# schematics.net
KiCad netlist of a schematic drawn in EAGLE
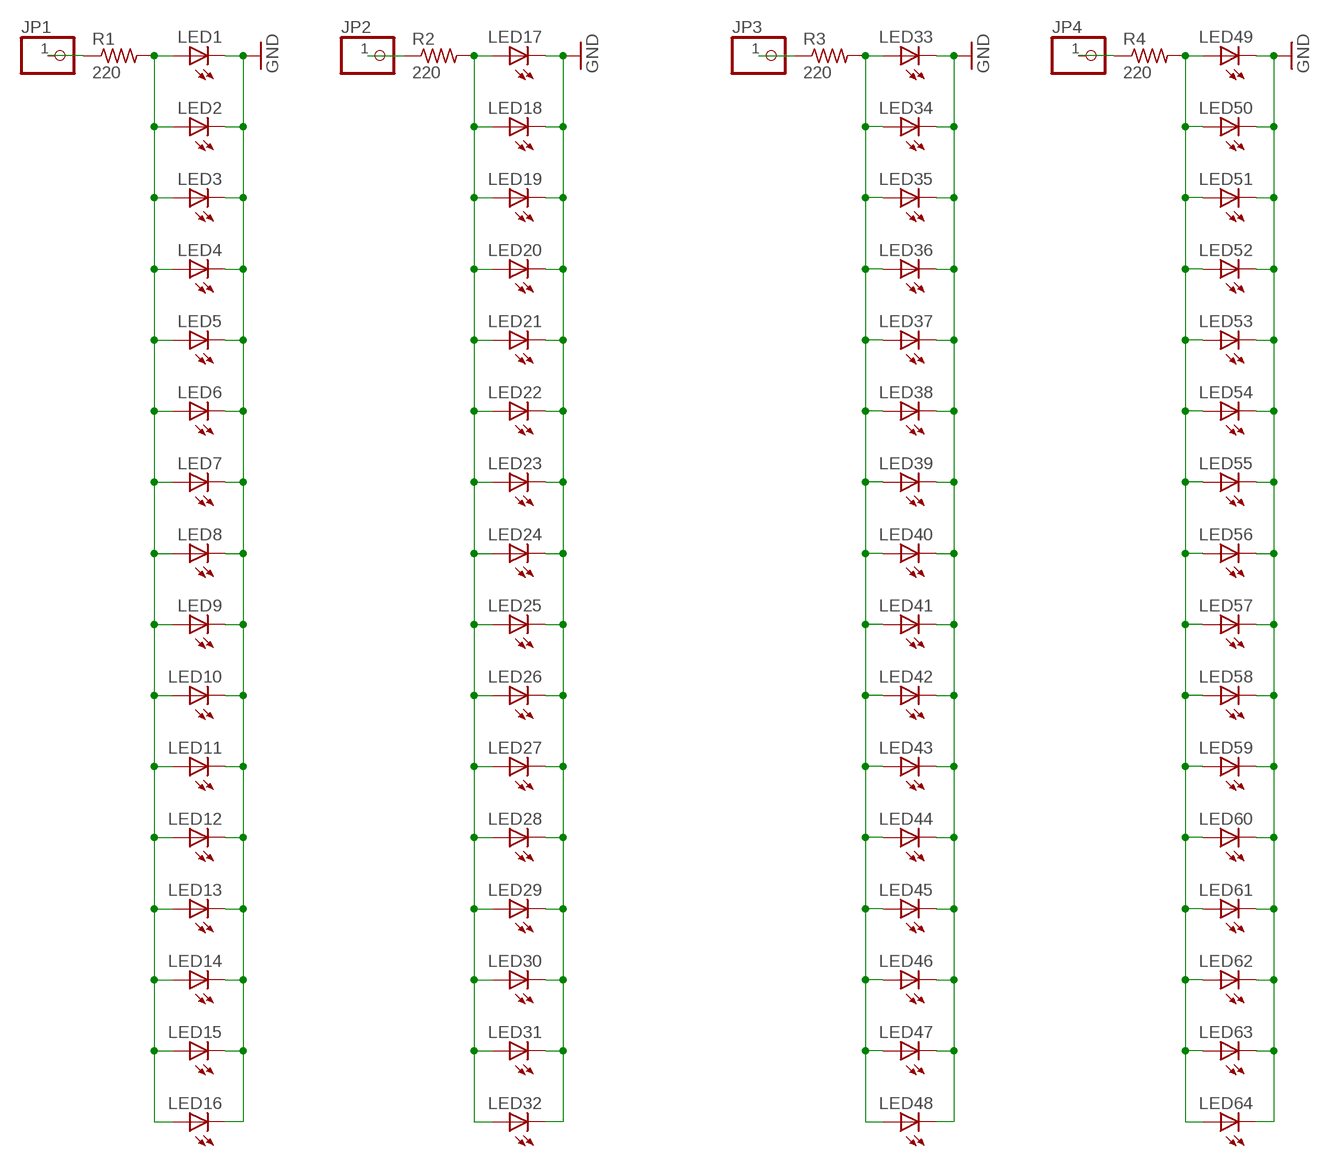
[diagram p0: schematic, sheet 1]

(export (version "E")
  (design (tool "Eeschema 10.0.6"))
  (components
    (comp (ref "JP1")
      (value "PINHD-1X1")
      (footprint "eagle-import:1X01")
      (libsource (lib "eagle-import") (part "PINHD-1X1"))
    )
    (comp (ref "JP2")
      (value "PINHD-1X1")
      (footprint "eagle-import:1X01")
      (libsource (lib "eagle-import") (part "PINHD-1X1"))
    )
    (comp (ref "JP3")
      (value "PINHD-1X1")
      (footprint "eagle-import:1X01")
      (libsource (lib "eagle-import") (part "PINHD-1X1"))
    )
    (comp (ref "JP4")
      (value "PINHD-1X1")
      (footprint "eagle-import:1X01")
      (libsource (lib "eagle-import") (part "PINHD-1X1"))
    )
    (comp (ref "LED1")
      (value "LED5MM")
      (footprint "eagle-import:LED5MM")
      (libsource (lib "eagle-import") (part "LED5MM"))
    )
    (comp (ref "LED2")
      (value "LED5MM")
      (footprint "eagle-import:LED5MM")
      (libsource (lib "eagle-import") (part "LED5MM"))
    )
    (comp (ref "LED3")
      (value "LED5MM")
      (footprint "eagle-import:LED5MM")
      (libsource (lib "eagle-import") (part "LED5MM"))
    )
    (comp (ref "LED4")
      (value "LED5MM")
      (footprint "eagle-import:LED5MM")
      (libsource (lib "eagle-import") (part "LED5MM"))
    )
    (comp (ref "LED5")
      (value "LED5MM")
      (footprint "eagle-import:LED5MM")
      (libsource (lib "eagle-import") (part "LED5MM"))
    )
    (comp (ref "LED6")
      (value "LED5MM")
      (footprint "eagle-import:LED5MM")
      (libsource (lib "eagle-import") (part "LED5MM"))
    )
    (comp (ref "LED7")
      (value "LED5MM")
      (footprint "eagle-import:LED5MM")
      (libsource (lib "eagle-import") (part "LED5MM"))
    )
    (comp (ref "LED8")
      (value "LED5MM")
      (footprint "eagle-import:LED5MM")
      (libsource (lib "eagle-import") (part "LED5MM"))
    )
    (comp (ref "LED9")
      (value "LED5MM")
      (footprint "eagle-import:LED5MM")
      (libsource (lib "eagle-import") (part "LED5MM"))
    )
    (comp (ref "LED10")
      (value "LED5MM")
      (footprint "eagle-import:LED5MM")
      (libsource (lib "eagle-import") (part "LED5MM"))
    )
    (comp (ref "LED11")
      (value "LED5MM")
      (footprint "eagle-import:LED5MM")
      (libsource (lib "eagle-import") (part "LED5MM"))
    )
    (comp (ref "LED12")
      (value "LED5MM")
      (footprint "eagle-import:LED5MM")
      (libsource (lib "eagle-import") (part "LED5MM"))
    )
    (comp (ref "LED13")
      (value "LED5MM")
      (footprint "eagle-import:LED5MM")
      (libsource (lib "eagle-import") (part "LED5MM"))
    )
    (comp (ref "LED14")
      (value "LED5MM")
      (footprint "eagle-import:LED5MM")
      (libsource (lib "eagle-import") (part "LED5MM"))
    )
    (comp (ref "LED15")
      (value "LED5MM")
      (footprint "eagle-import:LED5MM")
      (libsource (lib "eagle-import") (part "LED5MM"))
    )
    (comp (ref "LED16")
      (value "LED5MM")
      (footprint "eagle-import:LED5MM")
      (libsource (lib "eagle-import") (part "LED5MM"))
    )
    (comp (ref "LED17")
      (value "LED5MM")
      (footprint "eagle-import:LED5MM")
      (libsource (lib "eagle-import") (part "LED5MM"))
    )
    (comp (ref "LED18")
      (value "LED5MM")
      (footprint "eagle-import:LED5MM")
      (libsource (lib "eagle-import") (part "LED5MM"))
    )
    (comp (ref "LED19")
      (value "LED5MM")
      (footprint "eagle-import:LED5MM")
      (libsource (lib "eagle-import") (part "LED5MM"))
    )
    (comp (ref "LED20")
      (value "LED5MM")
      (footprint "eagle-import:LED5MM")
      (libsource (lib "eagle-import") (part "LED5MM"))
    )
    (comp (ref "LED21")
      (value "LED5MM")
      (footprint "eagle-import:LED5MM")
      (libsource (lib "eagle-import") (part "LED5MM"))
    )
    (comp (ref "LED22")
      (value "LED5MM")
      (footprint "eagle-import:LED5MM")
      (libsource (lib "eagle-import") (part "LED5MM"))
    )
    (comp (ref "LED23")
      (value "LED5MM")
      (footprint "eagle-import:LED5MM")
      (libsource (lib "eagle-import") (part "LED5MM"))
    )
    (comp (ref "LED24")
      (value "LED5MM")
      (footprint "eagle-import:LED5MM")
      (libsource (lib "eagle-import") (part "LED5MM"))
    )
    (comp (ref "LED25")
      (value "LED5MM")
      (footprint "eagle-import:LED5MM")
      (libsource (lib "eagle-import") (part "LED5MM"))
    )
    (comp (ref "LED26")
      (value "LED5MM")
      (footprint "eagle-import:LED5MM")
      (libsource (lib "eagle-import") (part "LED5MM"))
    )
    (comp (ref "LED27")
      (value "LED5MM")
      (footprint "eagle-import:LED5MM")
      (libsource (lib "eagle-import") (part "LED5MM"))
    )
    (comp (ref "LED28")
      (value "LED5MM")
      (footprint "eagle-import:LED5MM")
      (libsource (lib "eagle-import") (part "LED5MM"))
    )
    (comp (ref "LED29")
      (value "LED5MM")
      (footprint "eagle-import:LED5MM")
      (libsource (lib "eagle-import") (part "LED5MM"))
    )
    (comp (ref "LED30")
      (value "LED5MM")
      (footprint "eagle-import:LED5MM")
      (libsource (lib "eagle-import") (part "LED5MM"))
    )
    (comp (ref "LED31")
      (value "LED5MM")
      (footprint "eagle-import:LED5MM")
      (libsource (lib "eagle-import") (part "LED5MM"))
    )
    (comp (ref "LED32")
      (value "LED5MM")
      (footprint "eagle-import:LED5MM")
      (libsource (lib "eagle-import") (part "LED5MM"))
    )
    (comp (ref "LED33")
      (value "LED5MM")
      (footprint "eagle-import:LED5MM")
      (libsource (lib "eagle-import") (part "LED5MM"))
    )
    (comp (ref "LED34")
      (value "LED5MM")
      (footprint "eagle-import:LED5MM")
      (libsource (lib "eagle-import") (part "LED5MM"))
    )
    (comp (ref "LED35")
      (value "LED5MM")
      (footprint "eagle-import:LED5MM")
      (libsource (lib "eagle-import") (part "LED5MM"))
    )
    (comp (ref "LED36")
      (value "LED5MM")
      (footprint "eagle-import:LED5MM")
      (libsource (lib "eagle-import") (part "LED5MM"))
    )
    (comp (ref "LED37")
      (value "LED5MM")
      (footprint "eagle-import:LED5MM")
      (libsource (lib "eagle-import") (part "LED5MM"))
    )
    (comp (ref "LED38")
      (value "LED5MM")
      (footprint "eagle-import:LED5MM")
      (libsource (lib "eagle-import") (part "LED5MM"))
    )
    (comp (ref "LED39")
      (value "LED5MM")
      (footprint "eagle-import:LED5MM")
      (libsource (lib "eagle-import") (part "LED5MM"))
    )
    (comp (ref "LED40")
      (value "LED5MM")
      (footprint "eagle-import:LED5MM")
      (libsource (lib "eagle-import") (part "LED5MM"))
    )
    (comp (ref "LED41")
      (value "LED5MM")
      (footprint "eagle-import:LED5MM")
      (libsource (lib "eagle-import") (part "LED5MM"))
    )
    (comp (ref "LED42")
      (value "LED5MM")
      (footprint "eagle-import:LED5MM")
      (libsource (lib "eagle-import") (part "LED5MM"))
    )
    (comp (ref "LED43")
      (value "LED5MM")
      (footprint "eagle-import:LED5MM")
      (libsource (lib "eagle-import") (part "LED5MM"))
    )
    (comp (ref "LED44")
      (value "LED5MM")
      (footprint "eagle-import:LED5MM")
      (libsource (lib "eagle-import") (part "LED5MM"))
    )
    (comp (ref "LED45")
      (value "LED5MM")
      (footprint "eagle-import:LED5MM")
      (libsource (lib "eagle-import") (part "LED5MM"))
    )
    (comp (ref "LED46")
      (value "LED5MM")
      (footprint "eagle-import:LED5MM")
      (libsource (lib "eagle-import") (part "LED5MM"))
    )
    (comp (ref "LED47")
      (value "LED5MM")
      (footprint "eagle-import:LED5MM")
      (libsource (lib "eagle-import") (part "LED5MM"))
    )
    (comp (ref "LED48")
      (value "LED5MM")
      (footprint "eagle-import:LED5MM")
      (libsource (lib "eagle-import") (part "LED5MM"))
    )
    (comp (ref "LED49")
      (value "LED5MM")
      (footprint "eagle-import:LED5MM")
      (libsource (lib "eagle-import") (part "LED5MM"))
    )
    (comp (ref "LED50")
      (value "LED5MM")
      (footprint "eagle-import:LED5MM")
      (libsource (lib "eagle-import") (part "LED5MM"))
    )
    (comp (ref "LED51")
      (value "LED5MM")
      (footprint "eagle-import:LED5MM")
      (libsource (lib "eagle-import") (part "LED5MM"))
    )
    (comp (ref "LED52")
      (value "LED5MM")
      (footprint "eagle-import:LED5MM")
      (libsource (lib "eagle-import") (part "LED5MM"))
    )
    (comp (ref "LED53")
      (value "LED5MM")
      (footprint "eagle-import:LED5MM")
      (libsource (lib "eagle-import") (part "LED5MM"))
    )
    (comp (ref "LED54")
      (value "LED5MM")
      (footprint "eagle-import:LED5MM")
      (libsource (lib "eagle-import") (part "LED5MM"))
    )
    (comp (ref "LED55")
      (value "LED5MM")
      (footprint "eagle-import:LED5MM")
      (libsource (lib "eagle-import") (part "LED5MM"))
    )
    (comp (ref "LED56")
      (value "LED5MM")
      (footprint "eagle-import:LED5MM")
      (libsource (lib "eagle-import") (part "LED5MM"))
    )
    (comp (ref "LED57")
      (value "LED5MM")
      (footprint "eagle-import:LED5MM")
      (libsource (lib "eagle-import") (part "LED5MM"))
    )
    (comp (ref "LED58")
      (value "LED5MM")
      (footprint "eagle-import:LED5MM")
      (libsource (lib "eagle-import") (part "LED5MM"))
    )
    (comp (ref "LED59")
      (value "LED5MM")
      (footprint "eagle-import:LED5MM")
      (libsource (lib "eagle-import") (part "LED5MM"))
    )
    (comp (ref "LED60")
      (value "LED5MM")
      (footprint "eagle-import:LED5MM")
      (libsource (lib "eagle-import") (part "LED5MM"))
    )
    (comp (ref "LED61")
      (value "LED5MM")
      (footprint "eagle-import:LED5MM")
      (libsource (lib "eagle-import") (part "LED5MM"))
    )
    (comp (ref "LED62")
      (value "LED5MM")
      (footprint "eagle-import:LED5MM")
      (libsource (lib "eagle-import") (part "LED5MM"))
    )
    (comp (ref "LED63")
      (value "LED5MM")
      (footprint "eagle-import:LED5MM")
      (libsource (lib "eagle-import") (part "LED5MM"))
    )
    (comp (ref "LED64")
      (value "LED5MM")
      (footprint "eagle-import:LED5MM")
      (libsource (lib "eagle-import") (part "LED5MM"))
    )
    (comp (ref "R1")
      (value "220")
      (footprint "eagle-import:0204V")
      (libsource (lib "eagle-import") (part "R-US_0204/2V"))
    )
    (comp (ref "R2")
      (value "220")
      (footprint "eagle-import:0204V")
      (libsource (lib "eagle-import") (part "R-US_0204/2V"))
    )
    (comp (ref "R3")
      (value "220")
      (footprint "eagle-import:0204V")
      (libsource (lib "eagle-import") (part "R-US_0204/2V"))
    )
    (comp (ref "R4")
      (value "220")
      (footprint "eagle-import:0204V")
      (libsource (lib "eagle-import") (part "R-US_0204/2V"))
    )
  )
  (nets
    (net (code "1") (name "GND") (class "Default")
      (node (ref "LED1") (pin "K") (pinfunction "C_K") (pintype "passive"))
      (node (ref "LED10") (pin "K") (pinfunction "C_K") (pintype "passive"))
      (node (ref "LED11") (pin "K") (pinfunction "C_K") (pintype "passive"))
      (node (ref "LED12") (pin "K") (pinfunction "C_K") (pintype "passive"))
      (node (ref "LED13") (pin "K") (pinfunction "C_K") (pintype "passive"))
      (node (ref "LED14") (pin "K") (pinfunction "C_K") (pintype "passive"))
      (node (ref "LED15") (pin "K") (pinfunction "C_K") (pintype "passive"))
      (node (ref "LED16") (pin "K") (pinfunction "C_K") (pintype "passive"))
      (node (ref "LED17") (pin "K") (pinfunction "C_K") (pintype "passive"))
      (node (ref "LED18") (pin "K") (pinfunction "C_K") (pintype "passive"))
      (node (ref "LED19") (pin "K") (pinfunction "C_K") (pintype "passive"))
      (node (ref "LED2") (pin "K") (pinfunction "C_K") (pintype "passive"))
      (node (ref "LED20") (pin "K") (pinfunction "C_K") (pintype "passive"))
      (node (ref "LED21") (pin "K") (pinfunction "C_K") (pintype "passive"))
      (node (ref "LED22") (pin "K") (pinfunction "C_K") (pintype "passive"))
      (node (ref "LED23") (pin "K") (pinfunction "C_K") (pintype "passive"))
      (node (ref "LED24") (pin "K") (pinfunction "C_K") (pintype "passive"))
      (node (ref "LED25") (pin "K") (pinfunction "C_K") (pintype "passive"))
      (node (ref "LED26") (pin "K") (pinfunction "C_K") (pintype "passive"))
      (node (ref "LED27") (pin "K") (pinfunction "C_K") (pintype "passive"))
      (node (ref "LED28") (pin "K") (pinfunction "C_K") (pintype "passive"))
      (node (ref "LED29") (pin "K") (pinfunction "C_K") (pintype "passive"))
      (node (ref "LED3") (pin "K") (pinfunction "C_K") (pintype "passive"))
      (node (ref "LED30") (pin "K") (pinfunction "C_K") (pintype "passive"))
      (node (ref "LED31") (pin "K") (pinfunction "C_K") (pintype "passive"))
      (node (ref "LED32") (pin "K") (pinfunction "C_K") (pintype "passive"))
      (node (ref "LED33") (pin "K") (pinfunction "C_K") (pintype "passive"))
      (node (ref "LED34") (pin "K") (pinfunction "C_K") (pintype "passive"))
      (node (ref "LED35") (pin "K") (pinfunction "C_K") (pintype "passive"))
      (node (ref "LED36") (pin "K") (pinfunction "C_K") (pintype "passive"))
      (node (ref "LED37") (pin "K") (pinfunction "C_K") (pintype "passive"))
      (node (ref "LED38") (pin "K") (pinfunction "C_K") (pintype "passive"))
      (node (ref "LED39") (pin "K") (pinfunction "C_K") (pintype "passive"))
      (node (ref "LED4") (pin "K") (pinfunction "C_K") (pintype "passive"))
      (node (ref "LED40") (pin "K") (pinfunction "C_K") (pintype "passive"))
      (node (ref "LED41") (pin "K") (pinfunction "C_K") (pintype "passive"))
      (node (ref "LED42") (pin "K") (pinfunction "C_K") (pintype "passive"))
      (node (ref "LED43") (pin "K") (pinfunction "C_K") (pintype "passive"))
      (node (ref "LED44") (pin "K") (pinfunction "C_K") (pintype "passive"))
      (node (ref "LED45") (pin "K") (pinfunction "C_K") (pintype "passive"))
      (node (ref "LED46") (pin "K") (pinfunction "C_K") (pintype "passive"))
      (node (ref "LED47") (pin "K") (pinfunction "C_K") (pintype "passive"))
      (node (ref "LED48") (pin "K") (pinfunction "C_K") (pintype "passive"))
      (node (ref "LED49") (pin "K") (pinfunction "C_K") (pintype "passive"))
      (node (ref "LED5") (pin "K") (pinfunction "C_K") (pintype "passive"))
      (node (ref "LED50") (pin "K") (pinfunction "C_K") (pintype "passive"))
      (node (ref "LED51") (pin "K") (pinfunction "C_K") (pintype "passive"))
      (node (ref "LED52") (pin "K") (pinfunction "C_K") (pintype "passive"))
      (node (ref "LED53") (pin "K") (pinfunction "C_K") (pintype "passive"))
      (node (ref "LED54") (pin "K") (pinfunction "C_K") (pintype "passive"))
      (node (ref "LED55") (pin "K") (pinfunction "C_K") (pintype "passive"))
      (node (ref "LED56") (pin "K") (pinfunction "C_K") (pintype "passive"))
      (node (ref "LED57") (pin "K") (pinfunction "C_K") (pintype "passive"))
      (node (ref "LED58") (pin "K") (pinfunction "C_K") (pintype "passive"))
      (node (ref "LED59") (pin "K") (pinfunction "C_K") (pintype "passive"))
      (node (ref "LED6") (pin "K") (pinfunction "C_K") (pintype "passive"))
      (node (ref "LED60") (pin "K") (pinfunction "C_K") (pintype "passive"))
      (node (ref "LED61") (pin "K") (pinfunction "C_K") (pintype "passive"))
      (node (ref "LED62") (pin "K") (pinfunction "C_K") (pintype "passive"))
      (node (ref "LED63") (pin "K") (pinfunction "C_K") (pintype "passive"))
      (node (ref "LED64") (pin "K") (pinfunction "C_K") (pintype "passive"))
      (node (ref "LED7") (pin "K") (pinfunction "C_K") (pintype "passive"))
      (node (ref "LED8") (pin "K") (pinfunction "C_K") (pintype "passive"))
      (node (ref "LED9") (pin "K") (pinfunction "C_K") (pintype "passive"))
    )
    (net (code "2") (name "Net-(JP1-Pad1)") (class "Default")
      (node (ref "JP1") (pin "1") (pinfunction "1_1") (pintype "passive"))
      (node (ref "R1") (pin "1") (pinfunction "1_1") (pintype "passive"))
    )
    (net (code "3") (name "Net-(JP2-Pad1)") (class "Default")
      (node (ref "JP2") (pin "1") (pinfunction "1_1") (pintype "passive"))
      (node (ref "R2") (pin "1") (pinfunction "1_1") (pintype "passive"))
    )
    (net (code "4") (name "Net-(JP3-Pad1)") (class "Default")
      (node (ref "JP3") (pin "1") (pinfunction "1_1") (pintype "passive"))
      (node (ref "R3") (pin "1") (pinfunction "1_1") (pintype "passive"))
    )
    (net (code "5") (name "Net-(JP4-Pad1)") (class "Default")
      (node (ref "JP4") (pin "1") (pinfunction "1_1") (pintype "passive"))
      (node (ref "R4") (pin "1") (pinfunction "1_1") (pintype "passive"))
    )
    (net (code "6") (name "Net-(LED1-PadA)") (class "Default")
      (node (ref "LED1") (pin "A") (pinfunction "A_A") (pintype "passive"))
      (node (ref "LED10") (pin "A") (pinfunction "A_A") (pintype "passive"))
      (node (ref "LED11") (pin "A") (pinfunction "A_A") (pintype "passive"))
      (node (ref "LED12") (pin "A") (pinfunction "A_A") (pintype "passive"))
      (node (ref "LED13") (pin "A") (pinfunction "A_A") (pintype "passive"))
      (node (ref "LED14") (pin "A") (pinfunction "A_A") (pintype "passive"))
      (node (ref "LED15") (pin "A") (pinfunction "A_A") (pintype "passive"))
      (node (ref "LED16") (pin "A") (pinfunction "A_A") (pintype "passive"))
      (node (ref "LED2") (pin "A") (pinfunction "A_A") (pintype "passive"))
      (node (ref "LED3") (pin "A") (pinfunction "A_A") (pintype "passive"))
      (node (ref "LED4") (pin "A") (pinfunction "A_A") (pintype "passive"))
      (node (ref "LED5") (pin "A") (pinfunction "A_A") (pintype "passive"))
      (node (ref "LED6") (pin "A") (pinfunction "A_A") (pintype "passive"))
      (node (ref "LED7") (pin "A") (pinfunction "A_A") (pintype "passive"))
      (node (ref "LED8") (pin "A") (pinfunction "A_A") (pintype "passive"))
      (node (ref "LED9") (pin "A") (pinfunction "A_A") (pintype "passive"))
      (node (ref "R1") (pin "2") (pinfunction "2_2") (pintype "passive"))
    )
    (net (code "7") (name "Net-(LED17-PadA)") (class "Default")
      (node (ref "LED17") (pin "A") (pinfunction "A_A") (pintype "passive"))
      (node (ref "LED18") (pin "A") (pinfunction "A_A") (pintype "passive"))
      (node (ref "LED19") (pin "A") (pinfunction "A_A") (pintype "passive"))
      (node (ref "LED20") (pin "A") (pinfunction "A_A") (pintype "passive"))
      (node (ref "LED21") (pin "A") (pinfunction "A_A") (pintype "passive"))
      (node (ref "LED22") (pin "A") (pinfunction "A_A") (pintype "passive"))
      (node (ref "LED23") (pin "A") (pinfunction "A_A") (pintype "passive"))
      (node (ref "LED24") (pin "A") (pinfunction "A_A") (pintype "passive"))
      (node (ref "LED25") (pin "A") (pinfunction "A_A") (pintype "passive"))
      (node (ref "LED26") (pin "A") (pinfunction "A_A") (pintype "passive"))
      (node (ref "LED27") (pin "A") (pinfunction "A_A") (pintype "passive"))
      (node (ref "LED28") (pin "A") (pinfunction "A_A") (pintype "passive"))
      (node (ref "LED29") (pin "A") (pinfunction "A_A") (pintype "passive"))
      (node (ref "LED30") (pin "A") (pinfunction "A_A") (pintype "passive"))
      (node (ref "LED31") (pin "A") (pinfunction "A_A") (pintype "passive"))
      (node (ref "LED32") (pin "A") (pinfunction "A_A") (pintype "passive"))
      (node (ref "R2") (pin "2") (pinfunction "2_2") (pintype "passive"))
    )
    (net (code "8") (name "Net-(LED33-PadA)") (class "Default")
      (node (ref "LED33") (pin "A") (pinfunction "A_A") (pintype "passive"))
      (node (ref "LED34") (pin "A") (pinfunction "A_A") (pintype "passive"))
      (node (ref "LED35") (pin "A") (pinfunction "A_A") (pintype "passive"))
      (node (ref "LED36") (pin "A") (pinfunction "A_A") (pintype "passive"))
      (node (ref "LED37") (pin "A") (pinfunction "A_A") (pintype "passive"))
      (node (ref "LED38") (pin "A") (pinfunction "A_A") (pintype "passive"))
      (node (ref "LED39") (pin "A") (pinfunction "A_A") (pintype "passive"))
      (node (ref "LED40") (pin "A") (pinfunction "A_A") (pintype "passive"))
      (node (ref "LED41") (pin "A") (pinfunction "A_A") (pintype "passive"))
      (node (ref "LED42") (pin "A") (pinfunction "A_A") (pintype "passive"))
      (node (ref "LED43") (pin "A") (pinfunction "A_A") (pintype "passive"))
      (node (ref "LED44") (pin "A") (pinfunction "A_A") (pintype "passive"))
      (node (ref "LED45") (pin "A") (pinfunction "A_A") (pintype "passive"))
      (node (ref "LED46") (pin "A") (pinfunction "A_A") (pintype "passive"))
      (node (ref "LED47") (pin "A") (pinfunction "A_A") (pintype "passive"))
      (node (ref "LED48") (pin "A") (pinfunction "A_A") (pintype "passive"))
      (node (ref "R3") (pin "2") (pinfunction "2_2") (pintype "passive"))
    )
    (net (code "9") (name "Net-(LED49-PadA)") (class "Default")
      (node (ref "LED49") (pin "A") (pinfunction "A_A") (pintype "passive"))
      (node (ref "LED50") (pin "A") (pinfunction "A_A") (pintype "passive"))
      (node (ref "LED51") (pin "A") (pinfunction "A_A") (pintype "passive"))
      (node (ref "LED52") (pin "A") (pinfunction "A_A") (pintype "passive"))
      (node (ref "LED53") (pin "A") (pinfunction "A_A") (pintype "passive"))
      (node (ref "LED54") (pin "A") (pinfunction "A_A") (pintype "passive"))
      (node (ref "LED55") (pin "A") (pinfunction "A_A") (pintype "passive"))
      (node (ref "LED56") (pin "A") (pinfunction "A_A") (pintype "passive"))
      (node (ref "LED57") (pin "A") (pinfunction "A_A") (pintype "passive"))
      (node (ref "LED58") (pin "A") (pinfunction "A_A") (pintype "passive"))
      (node (ref "LED59") (pin "A") (pinfunction "A_A") (pintype "passive"))
      (node (ref "LED60") (pin "A") (pinfunction "A_A") (pintype "passive"))
      (node (ref "LED61") (pin "A") (pinfunction "A_A") (pintype "passive"))
      (node (ref "LED62") (pin "A") (pinfunction "A_A") (pintype "passive"))
      (node (ref "LED63") (pin "A") (pinfunction "A_A") (pintype "passive"))
      (node (ref "LED64") (pin "A") (pinfunction "A_A") (pintype "passive"))
      (node (ref "R4") (pin "2") (pinfunction "2_2") (pintype "passive"))
    )
  )
)
